# Indicators.net
KiCad netlist of a schematic drawn in Altium Designer
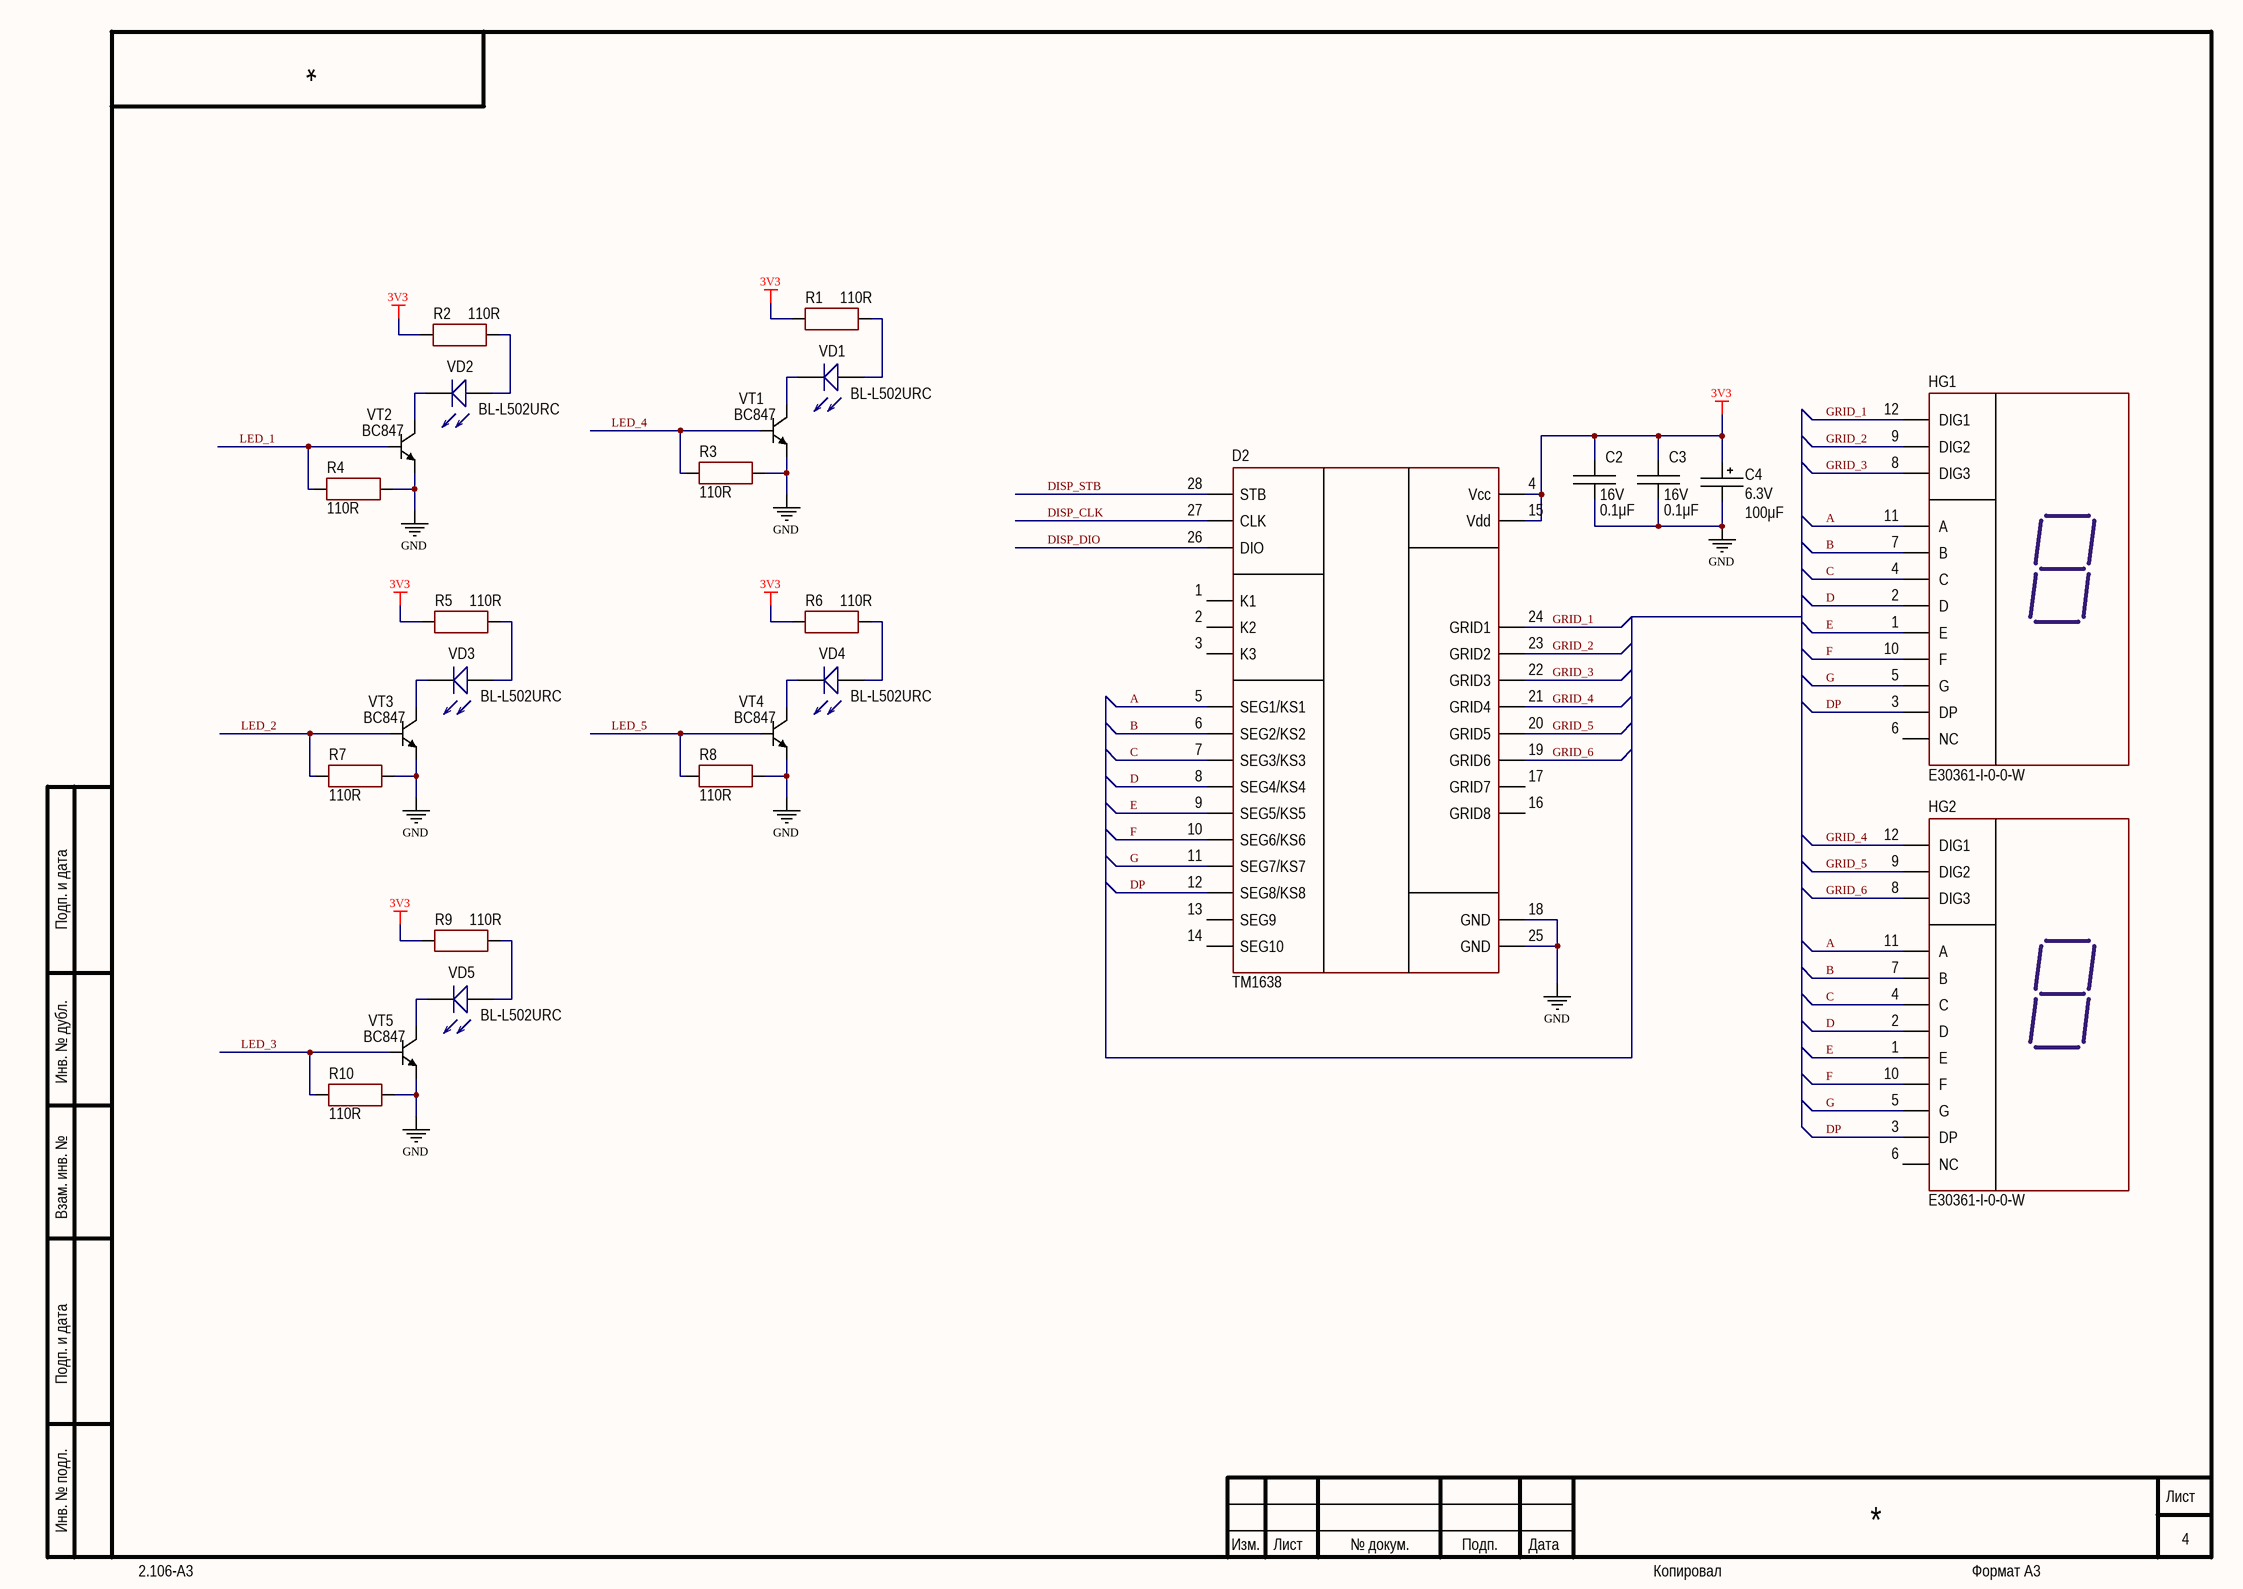
[diagram p0: Indicators.SchDoc]

(export (version "E")
  (design (tool "Eeschema 10.0.6"))
  (components
    (comp (ref "C2")
      (value "0.1μF")
      (footprint "CAP: 0805")
      (fields
        (field (name "MANUFACTURER") "Yageo")
        (field (name "PARTNUMBER") "CC0805KRX7R7BB104")
        (field (name "VALUEMANUFACTURERPARTNUMBER") "Ceramic capacitor, 0.1μF, X7R, ±10%, 16V, 0805, -55...+125°C")
        (field (name "VOLTAGE") "16V")
      )
      (libsource (lib "capacitor") (part "Ceramic_0805"))
    )
    (comp (ref "C3")
      (value "0.1μF")
      (footprint "CAP: 0805")
      (fields
        (field (name "MANUFACTURER") "Yageo")
        (field (name "PARTNUMBER") "CC0805KRX7R7BB104")
        (field (name "VALUEMANUFACTURERPARTNUMBER") "Ceramic capacitor, 0.1μF, X7R, ±10%, 16V, 0805, -55...+125°C")
        (field (name "VOLTAGE") "16V")
      )
      (libsource (lib "capacitor") (part "Ceramic_0805"))
    )
    (comp (ref "C4")
      (value "100μF")
      (footprint "CAP: TANTAL-C")
      (fields
        (field (name "MANUFACTURER") "AVX")
        (field (name "PARTNUMBER") "F931E226MCC")
        (field (name "VALUEMANUFACTURERPARTNUMBER") "Tantalum capacitor, 100μF, 6.3V, ±10%, 1.1Ohm, case C (6032), -55...+125°C")
        (field (name "VOLTAGE") "6.3V")
      )
      (libsource (lib "capacitor") (part "Tantal_C"))
    )
    (comp (ref "D2")
      (value "~")
      (footprint "28-SOP")
      (description "7-seg LED Driver")
      (fields
        (field (name "MANUFACTURER") "TM(Shenzhen Titan Micro Elec)")
        (field (name "VALUEMANUFACTURERPARTNUMBER") "LED Display driver, 480 Mb/s, ULPI, USB, 3...3.6V, -40...+85°C, SOP-28")
        (field (name "PARTNUMBER") "TM1638")
      )
      (libsource (lib "ic-interface") (part "TM1638"))
    )
    (comp (ref "HG1")
      (value "~")
      (footprint "DISP: CL3631BH - GREEN (0,36\")")
      (description "7 segment LED indicator 3 dig")
      (fields
        (field (name "VALUEMANUFACTURERPARTNUMBER") "7Seg LED, , , , -40...+85°C, 14х22,5")
        (field (name "PARTNUMBER") "E30361-I-0-0-W")
      )
      (libsource (lib "module") (part "E30361"))
    )
    (comp (ref "HG2")
      (value "~")
      (footprint "DISP: CL3631BH - GREEN (0,36\")")
      (description "7 segment LED indicator 3 dig")
      (fields
        (field (name "VALUEMANUFACTURERPARTNUMBER") "7Seg LED, , , , -40...+85°C, 14х22,5")
        (field (name "PARTNUMBER") "E30361-I-0-0-W")
      )
      (libsource (lib "module") (part "E30361"))
    )
    (comp (ref "R1")
      (value "110R")
      (footprint "RES: 1206")
      (fields
        (field (name "MANUFACTURER") "Yageo")
        (field (name "PARTNUMBER") "RC1206JR-07100RL")
        (field (name "VALUEMANUFACTURERPARTNUMBER") "Resistor film, 110R, ±5%, 1206, 0.25W, -55...+125°C")
      )
      (libsource (lib "resistor") (part "Resistor_1206"))
    )
    (comp (ref "R2")
      (value "110R")
      (footprint "RES: 1206")
      (fields
        (field (name "MANUFACTURER") "Yageo")
        (field (name "PARTNUMBER") "RC1206JR-07100RL")
        (field (name "VALUEMANUFACTURERPARTNUMBER") "Resistor film, 110R, ±5%, 1206, 0.25W, -55...+125°C")
      )
      (libsource (lib "resistor") (part "Resistor_1206"))
    )
    (comp (ref "R3")
      (value "110R")
      (footprint "RES: 1206")
      (fields
        (field (name "MANUFACTURER") "Yageo")
        (field (name "PARTNUMBER") "RC1206JR-07100RL")
        (field (name "VALUEMANUFACTURERPARTNUMBER") "Resistor film, 110R, ±5%, 1206, 0.25W, -55...+125°C")
      )
      (libsource (lib "resistor") (part "Resistor_1206"))
    )
    (comp (ref "R4")
      (value "110R")
      (footprint "RES: 1206")
      (fields
        (field (name "MANUFACTURER") "Yageo")
        (field (name "PARTNUMBER") "RC1206JR-07100RL")
        (field (name "VALUEMANUFACTURERPARTNUMBER") "Resistor film, 110R, ±5%, 1206, 0.25W, -55...+125°C")
      )
      (libsource (lib "resistor") (part "Resistor_1206"))
    )
    (comp (ref "R5")
      (value "110R")
      (footprint "RES: 1206")
      (fields
        (field (name "MANUFACTURER") "Yageo")
        (field (name "PARTNUMBER") "RC1206JR-07100RL")
        (field (name "VALUEMANUFACTURERPARTNUMBER") "Resistor film, 110R, ±5%, 1206, 0.25W, -55...+125°C")
      )
      (libsource (lib "resistor") (part "Resistor_1206"))
    )
    (comp (ref "R6")
      (value "110R")
      (footprint "RES: 1206")
      (fields
        (field (name "MANUFACTURER") "Yageo")
        (field (name "PARTNUMBER") "RC1206JR-07100RL")
        (field (name "VALUEMANUFACTURERPARTNUMBER") "Resistor film, 110R, ±5%, 1206, 0.25W, -55...+125°C")
      )
      (libsource (lib "resistor") (part "Resistor_1206"))
    )
    (comp (ref "R7")
      (value "110R")
      (footprint "RES: 1206")
      (fields
        (field (name "MANUFACTURER") "Yageo")
        (field (name "PARTNUMBER") "RC1206JR-07100RL")
        (field (name "VALUEMANUFACTURERPARTNUMBER") "Resistor film, 110R, ±5%, 1206, 0.25W, -55...+125°C")
      )
      (libsource (lib "resistor") (part "Resistor_1206"))
    )
    (comp (ref "R8")
      (value "110R")
      (footprint "RES: 1206")
      (fields
        (field (name "MANUFACTURER") "Yageo")
        (field (name "PARTNUMBER") "RC1206JR-07100RL")
        (field (name "VALUEMANUFACTURERPARTNUMBER") "Resistor film, 110R, ±5%, 1206, 0.25W, -55...+125°C")
      )
      (libsource (lib "resistor") (part "Resistor_1206"))
    )
    (comp (ref "R9")
      (value "110R")
      (footprint "RES: 1206")
      (fields
        (field (name "MANUFACTURER") "Yageo")
        (field (name "PARTNUMBER") "RC1206JR-07100RL")
        (field (name "VALUEMANUFACTURERPARTNUMBER") "Resistor film, 110R, ±5%, 1206, 0.25W, -55...+125°C")
      )
      (libsource (lib "resistor") (part "Resistor_1206"))
    )
    (comp (ref "R10")
      (value "110R")
      (footprint "RES: 1206")
      (fields
        (field (name "MANUFACTURER") "Yageo")
        (field (name "PARTNUMBER") "RC1206JR-07100RL")
        (field (name "VALUEMANUFACTURERPARTNUMBER") "Resistor film, 110R, ±5%, 1206, 0.25W, -55...+125°C")
      )
      (libsource (lib "resistor") (part "Resistor_1206"))
    )
    (comp (ref "VD1")
      (value "LED")
      (footprint "LED 5mm RED")
      (description "BL-L502URC")
      (fields (field (name "PARTNUMBER") "BL-L502URC"))
      (libsource (lib "my_library") (part "LED"))
    )
    (comp (ref "VD2")
      (value "LED")
      (footprint "LED 5mm RED")
      (description "BL-L502URC")
      (fields (field (name "PARTNUMBER") "BL-L502URC"))
      (libsource (lib "my_library") (part "LED"))
    )
    (comp (ref "VD3")
      (value "LED")
      (footprint "LED 5mm RED")
      (description "BL-L502URC")
      (fields (field (name "PARTNUMBER") "BL-L502URC"))
      (libsource (lib "my_library") (part "LED"))
    )
    (comp (ref "VD4")
      (value "LED")
      (footprint "LED 5mm RED")
      (description "BL-L502URC")
      (fields (field (name "PARTNUMBER") "BL-L502URC"))
      (libsource (lib "my_library") (part "LED"))
    )
    (comp (ref "VD5")
      (value "LED")
      (footprint "LED 5mm RED")
      (description "BL-L502URC")
      (fields (field (name "PARTNUMBER") "BL-L502URC"))
      (libsource (lib "my_library") (part "LED"))
    )
    (comp (ref "VT1")
      (value "~")
      (footprint "SOT23")
      (fields
        (field (name "MANUFACTURER") "ON Semiconductor")
        (field (name "VALUEMANUFACTURERPARTNUMBER") "NPN transistor, 45V, 100mA, 100MHz, 300mW, 0.6V, 420, SOT-23, -55...+125°C")
        (field (name "PARTNUMBER") "BC847")
      )
      (libsource (lib "transistor") (part "BJT_NPN_132"))
    )
    (comp (ref "VT2")
      (value "~")
      (footprint "SOT23")
      (fields
        (field (name "MANUFACTURER") "ON Semiconductor")
        (field (name "VALUEMANUFACTURERPARTNUMBER") "NPN transistor, 45V, 100mA, 100MHz, 300mW, 0.6V, 420, SOT-23, -55...+125°C")
        (field (name "PARTNUMBER") "BC847")
      )
      (libsource (lib "transistor") (part "BJT_NPN_132"))
    )
    (comp (ref "VT3")
      (value "~")
      (footprint "SOT23")
      (fields
        (field (name "MANUFACTURER") "ON Semiconductor")
        (field (name "VALUEMANUFACTURERPARTNUMBER") "NPN transistor, 45V, 100mA, 100MHz, 300mW, 0.6V, 420, SOT-23, -55...+125°C")
        (field (name "PARTNUMBER") "BC847")
      )
      (libsource (lib "transistor") (part "BJT_NPN_132"))
    )
    (comp (ref "VT4")
      (value "~")
      (footprint "SOT23")
      (fields
        (field (name "MANUFACTURER") "ON Semiconductor")
        (field (name "VALUEMANUFACTURERPARTNUMBER") "NPN transistor, 45V, 100mA, 100MHz, 300mW, 0.6V, 420, SOT-23, -55...+125°C")
        (field (name "PARTNUMBER") "BC847")
      )
      (libsource (lib "transistor") (part "BJT_NPN_132"))
    )
    (comp (ref "VT5")
      (value "~")
      (footprint "SOT23")
      (fields
        (field (name "MANUFACTURER") "ON Semiconductor")
        (field (name "VALUEMANUFACTURERPARTNUMBER") "NPN transistor, 45V, 100mA, 100MHz, 300mW, 0.6V, 420, SOT-23, -55...+125°C")
        (field (name "PARTNUMBER") "BC847")
      )
      (libsource (lib "transistor") (part "BJT_NPN_132"))
    )
  )
  (nets
    (net (code "1") (name "/A") (class "Default")
      (node (ref "D2") (pin "5") (pinfunction "SEG1/KS1_5") (pintype "passive"))
      (node (ref "HG1") (pin "11") (pinfunction "A_11") (pintype "passive"))
      (node (ref "HG2") (pin "11") (pinfunction "A_11") (pintype "passive"))
    )
    (net (code "2") (name "/B") (class "Default")
      (node (ref "D2") (pin "6") (pinfunction "SEG2/KS2_6") (pintype "passive"))
      (node (ref "HG1") (pin "7") (pinfunction "B_7") (pintype "passive"))
      (node (ref "HG2") (pin "7") (pinfunction "B_7") (pintype "passive"))
    )
    (net (code "3") (name "/C") (class "Default")
      (node (ref "D2") (pin "7") (pinfunction "SEG3/KS3_7") (pintype "passive"))
      (node (ref "HG1") (pin "4") (pinfunction "C_4") (pintype "passive"))
      (node (ref "HG2") (pin "4") (pinfunction "C_4") (pintype "passive"))
    )
    (net (code "4") (name "/D") (class "Default")
      (node (ref "D2") (pin "8") (pinfunction "SEG4/KS4_8") (pintype "passive"))
      (node (ref "HG1") (pin "2") (pinfunction "D_2") (pintype "passive"))
      (node (ref "HG2") (pin "2") (pinfunction "D_2") (pintype "passive"))
    )
    (net (code "5") (name "/DISP_CLK") (class "Default")
      (node (ref "D2") (pin "27") (pinfunction "CLK_27") (pintype "passive"))
    )
    (net (code "6") (name "/DISP_DIO") (class "Default")
      (node (ref "D2") (pin "26") (pinfunction "DIO_26") (pintype "passive"))
    )
    (net (code "7") (name "/DISP_STB") (class "Default")
      (node (ref "D2") (pin "28") (pinfunction "STB_28") (pintype "passive"))
    )
    (net (code "8") (name "/DP") (class "Default")
      (node (ref "D2") (pin "12") (pinfunction "SEG8/KS8_12") (pintype "passive"))
      (node (ref "HG1") (pin "3") (pinfunction "DP_3") (pintype "passive"))
      (node (ref "HG2") (pin "3") (pinfunction "DP_3") (pintype "passive"))
    )
    (net (code "9") (name "/E") (class "Default")
      (node (ref "D2") (pin "9") (pinfunction "SEG5/KS5_9") (pintype "passive"))
      (node (ref "HG1") (pin "1") (pinfunction "E_1") (pintype "passive"))
      (node (ref "HG2") (pin "1") (pinfunction "E_1") (pintype "passive"))
    )
    (net (code "10") (name "/F") (class "Default")
      (node (ref "D2") (pin "10") (pinfunction "SEG6/KS6_10") (pintype "passive"))
      (node (ref "HG1") (pin "10") (pinfunction "F_10") (pintype "passive"))
      (node (ref "HG2") (pin "10") (pinfunction "F_10") (pintype "passive"))
    )
    (net (code "11") (name "/G") (class "Default")
      (node (ref "D2") (pin "11") (pinfunction "SEG7/KS7_11") (pintype "passive"))
      (node (ref "HG1") (pin "5") (pinfunction "G_5") (pintype "passive"))
      (node (ref "HG2") (pin "5") (pinfunction "G_5") (pintype "passive"))
    )
    (net (code "12") (name "/GRID_1") (class "Default")
      (node (ref "D2") (pin "24") (pinfunction "GRID1_24") (pintype "passive"))
      (node (ref "HG1") (pin "12") (pinfunction "DIG1_12") (pintype "passive"))
    )
    (net (code "13") (name "/GRID_2") (class "Default")
      (node (ref "D2") (pin "23") (pinfunction "GRID2_23") (pintype "passive"))
      (node (ref "HG1") (pin "9") (pinfunction "DIG2_9") (pintype "passive"))
    )
    (net (code "14") (name "/GRID_3") (class "Default")
      (node (ref "D2") (pin "22") (pinfunction "GRID3_22") (pintype "passive"))
      (node (ref "HG1") (pin "8") (pinfunction "DIG3_8") (pintype "passive"))
    )
    (net (code "15") (name "/GRID_4") (class "Default")
      (node (ref "D2") (pin "21") (pinfunction "GRID4_21") (pintype "passive"))
      (node (ref "HG2") (pin "12") (pinfunction "DIG1_12") (pintype "passive"))
    )
    (net (code "16") (name "/GRID_5") (class "Default")
      (node (ref "D2") (pin "20") (pinfunction "GRID5_20") (pintype "passive"))
      (node (ref "HG2") (pin "9") (pinfunction "DIG2_9") (pintype "passive"))
    )
    (net (code "17") (name "/GRID_6") (class "Default")
      (node (ref "D2") (pin "19") (pinfunction "GRID6_19") (pintype "passive"))
      (node (ref "HG2") (pin "8") (pinfunction "DIG3_8") (pintype "passive"))
    )
    (net (code "18") (name "/LED_1") (class "Default")
      (node (ref "R4") (pin "2") (pinfunction "2_2") (pintype "passive"))
      (node (ref "VT2") (pin "1") (pinfunction "B_1") (pintype "passive"))
    )
    (net (code "19") (name "/LED_2") (class "Default")
      (node (ref "R7") (pin "2") (pinfunction "2_2") (pintype "passive"))
      (node (ref "VT3") (pin "1") (pinfunction "B_1") (pintype "passive"))
    )
    (net (code "20") (name "/LED_3") (class "Default")
      (node (ref "R10") (pin "2") (pinfunction "2_2") (pintype "passive"))
      (node (ref "VT5") (pin "1") (pinfunction "B_1") (pintype "passive"))
    )
    (net (code "21") (name "/LED_4") (class "Default")
      (node (ref "R3") (pin "2") (pinfunction "2_2") (pintype "passive"))
      (node (ref "VT1") (pin "1") (pinfunction "B_1") (pintype "passive"))
    )
    (net (code "22") (name "/LED_5") (class "Default")
      (node (ref "R8") (pin "2") (pinfunction "2_2") (pintype "passive"))
      (node (ref "VT4") (pin "1") (pinfunction "B_1") (pintype "passive"))
    )
    (net (code "23") (name "3V3") (class "Default")
      (node (ref "C2") (pin "2") (pinfunction "2_2") (pintype "passive"))
      (node (ref "C3") (pin "2") (pinfunction "2_2") (pintype "passive"))
      (node (ref "C4") (pin "1") (pinfunction "1_1") (pintype "passive"))
      (node (ref "D2") (pin "15") (pinfunction "Vdd_15") (pintype "passive"))
      (node (ref "D2") (pin "4") (pinfunction "Vcc_4") (pintype "passive"))
      (node (ref "R1") (pin "2") (pinfunction "2_2") (pintype "passive"))
      (node (ref "R2") (pin "2") (pinfunction "2_2") (pintype "passive"))
      (node (ref "R5") (pin "2") (pinfunction "2_2") (pintype "passive"))
      (node (ref "R6") (pin "2") (pinfunction "2_2") (pintype "passive"))
      (node (ref "R9") (pin "2") (pinfunction "2_2") (pintype "passive"))
    )
    (net (code "24") (name "GND") (class "Default")
      (node (ref "C2") (pin "1") (pinfunction "1_1") (pintype "passive"))
      (node (ref "C3") (pin "1") (pinfunction "1_1") (pintype "passive"))
      (node (ref "C4") (pin "2") (pinfunction "2_2") (pintype "passive"))
      (node (ref "D2") (pin "18") (pinfunction "GND_18") (pintype "passive"))
      (node (ref "D2") (pin "25") (pinfunction "GND_25") (pintype "passive"))
      (node (ref "R10") (pin "1") (pinfunction "1_1") (pintype "passive"))
      (node (ref "R3") (pin "1") (pinfunction "1_1") (pintype "passive"))
      (node (ref "R4") (pin "1") (pinfunction "1_1") (pintype "passive"))
      (node (ref "R7") (pin "1") (pinfunction "1_1") (pintype "passive"))
      (node (ref "R8") (pin "1") (pinfunction "1_1") (pintype "passive"))
      (node (ref "VT1") (pin "2") (pinfunction "E_2") (pintype "passive"))
      (node (ref "VT2") (pin "2") (pinfunction "E_2") (pintype "passive"))
      (node (ref "VT3") (pin "2") (pinfunction "E_2") (pintype "passive"))
      (node (ref "VT4") (pin "2") (pinfunction "E_2") (pintype "passive"))
      (node (ref "VT5") (pin "2") (pinfunction "E_2") (pintype "passive"))
    )
    (net (code "25") (name "Net-(R1-Pad1)") (class "Default")
      (node (ref "R1") (pin "1") (pinfunction "1_1") (pintype "passive"))
      (node (ref "VD1") (pin "2") (pinfunction "2_2") (pintype "passive"))
    )
    (net (code "26") (name "Net-(R2-Pad1)") (class "Default")
      (node (ref "R2") (pin "1") (pinfunction "1_1") (pintype "passive"))
      (node (ref "VD2") (pin "2") (pinfunction "2_2") (pintype "passive"))
    )
    (net (code "27") (name "Net-(R5-Pad1)") (class "Default")
      (node (ref "R5") (pin "1") (pinfunction "1_1") (pintype "passive"))
      (node (ref "VD3") (pin "2") (pinfunction "2_2") (pintype "passive"))
    )
    (net (code "28") (name "Net-(R6-Pad1)") (class "Default")
      (node (ref "R6") (pin "1") (pinfunction "1_1") (pintype "passive"))
      (node (ref "VD4") (pin "2") (pinfunction "2_2") (pintype "passive"))
    )
    (net (code "29") (name "Net-(R9-Pad1)") (class "Default")
      (node (ref "R9") (pin "1") (pinfunction "1_1") (pintype "passive"))
      (node (ref "VD5") (pin "2") (pinfunction "2_2") (pintype "passive"))
    )
    (net (code "30") (name "Net-(VT1-C)") (class "Default")
      (node (ref "VD1") (pin "1") (pinfunction "1_1") (pintype "passive"))
      (node (ref "VT1") (pin "3") (pinfunction "C_3") (pintype "passive"))
    )
    (net (code "31") (name "Net-(VT2-C)") (class "Default")
      (node (ref "VD2") (pin "1") (pinfunction "1_1") (pintype "passive"))
      (node (ref "VT2") (pin "3") (pinfunction "C_3") (pintype "passive"))
    )
    (net (code "32") (name "Net-(VT3-C)") (class "Default")
      (node (ref "VD3") (pin "1") (pinfunction "1_1") (pintype "passive"))
      (node (ref "VT3") (pin "3") (pinfunction "C_3") (pintype "passive"))
    )
    (net (code "33") (name "Net-(VT4-C)") (class "Default")
      (node (ref "VD4") (pin "1") (pinfunction "1_1") (pintype "passive"))
      (node (ref "VT4") (pin "3") (pinfunction "C_3") (pintype "passive"))
    )
    (net (code "34") (name "Net-(VT5-C)") (class "Default")
      (node (ref "VD5") (pin "1") (pinfunction "1_1") (pintype "passive"))
      (node (ref "VT5") (pin "3") (pinfunction "C_3") (pintype "passive"))
    )
    (net (code "35") (name "unconnected-(D2-GRID7-Pad17)") (class "Default")
      (node (ref "D2") (pin "17") (pinfunction "GRID7_17") (pintype "passive"))
    )
    (net (code "36") (name "unconnected-(D2-GRID8-Pad16)") (class "Default")
      (node (ref "D2") (pin "16") (pinfunction "GRID8_16") (pintype "passive"))
    )
    (net (code "37") (name "unconnected-(D2-K1-Pad1)") (class "Default")
      (node (ref "D2") (pin "1") (pinfunction "K1_1") (pintype "passive"))
    )
    (net (code "38") (name "unconnected-(D2-K2-Pad2)") (class "Default")
      (node (ref "D2") (pin "2") (pinfunction "K2_2") (pintype "passive"))
    )
    (net (code "39") (name "unconnected-(D2-K3-Pad3)") (class "Default")
      (node (ref "D2") (pin "3") (pinfunction "K3_3") (pintype "passive"))
    )
    (net (code "40") (name "unconnected-(D2-SEG9-Pad13)") (class "Default")
      (node (ref "D2") (pin "13") (pinfunction "SEG9_13") (pintype "passive"))
    )
    (net (code "41") (name "unconnected-(D2-SEG10-Pad14)") (class "Default")
      (node (ref "D2") (pin "14") (pinfunction "SEG10_14") (pintype "passive"))
    )
    (net (code "42") (name "unconnected-(HG1-NC-Pad6)") (class "Default")
      (node (ref "HG1") (pin "6") (pinfunction "NC_6") (pintype "passive"))
    )
    (net (code "43") (name "unconnected-(HG2-NC-Pad6)") (class "Default")
      (node (ref "HG2") (pin "6") (pinfunction "NC_6") (pintype "passive"))
    )
  )
)
